# STM32_PCB_Design.net
KiCad netlist of a schematic drawn in Altium Designer
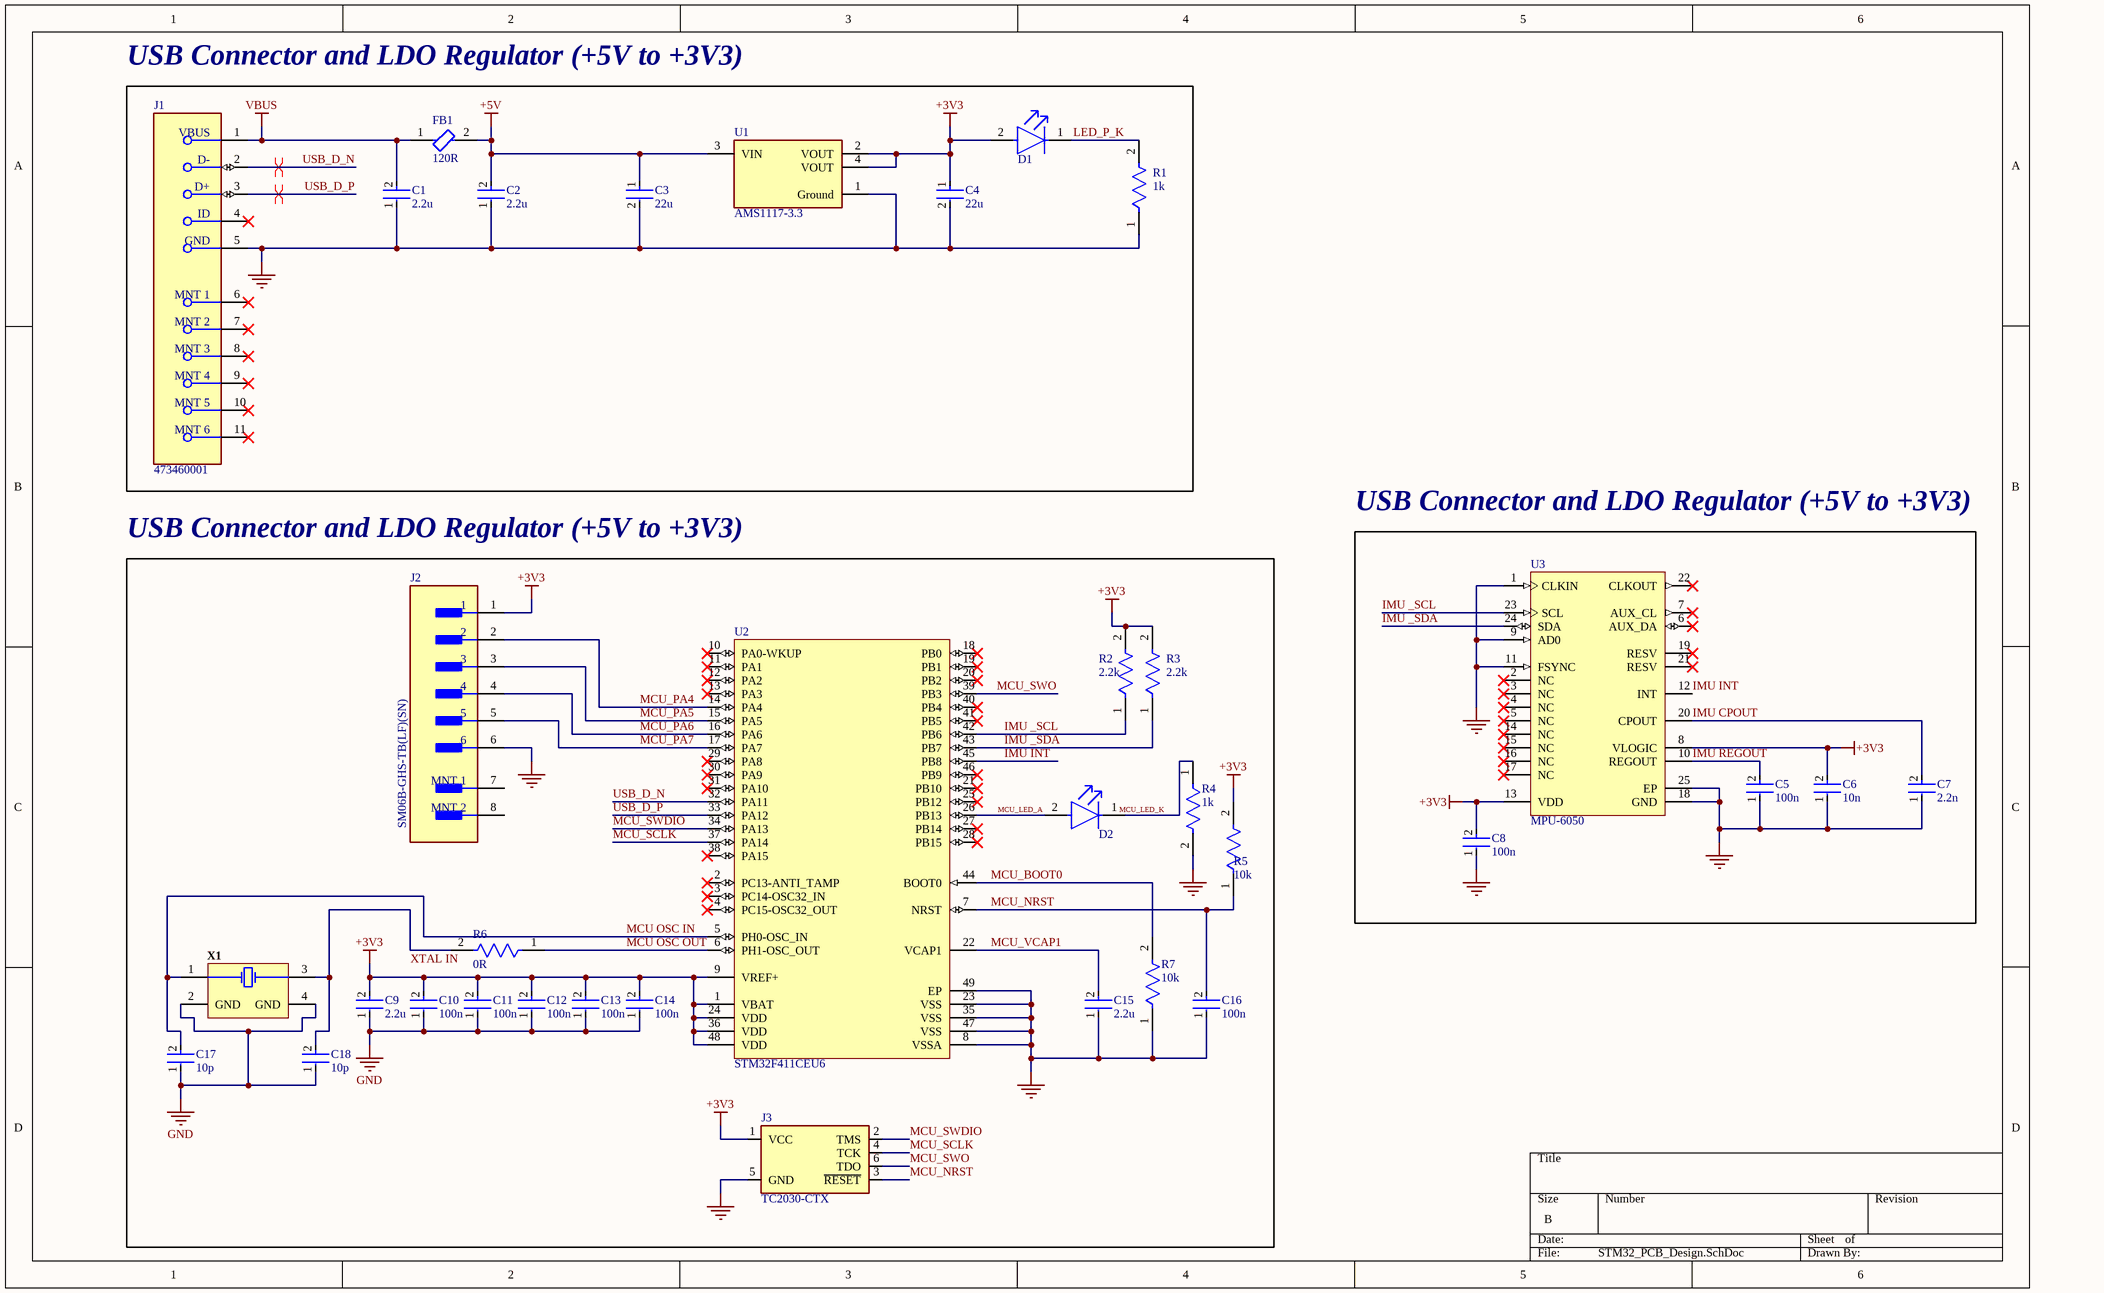
[diagram p0: STM32_PCB_Design.SchDoc]

(export (version "E")
  (design (tool "Eeschema 10.0.6"))
  (components
    (comp (ref "C1")
      (value "2.2u")
      (footprint "FP-GRM15-MFG")
      (description "CAP CER 0.1UF 16V X7R 0402")
      (fields (field (name "MANUFACTURER PART NUMBER") "GRM155R71C104KA88D") (field (name "TOLERANCE") "10%"))
      (libsource (lib "Altium Content Vault") (part "236180d848d6139a670b325ea6854c9"))
    )
    (comp (ref "C2")
      (value "2.2u")
      (footprint "FP-GRM15-MFG")
      (description "CAP CER 0.1UF 16V X7R 0402")
      (fields (field (name "MANUFACTURER PART NUMBER") "GRM155R71C104KA88D") (field (name "TOLERANCE") "10%"))
      (libsource (lib "Altium Content Vault") (part "236180d848d6139a670b325ea6854c9"))
    )
    (comp (ref "C3")
      (value "22u")
      (footprint "FP-0805-L_2_01_0_2-W_1_25-IPC_C")
      (description "General Purpose Ceramic Capacitor, 0805, 100nF, 10%, X7R, 0.15, 50V")
      (fields (field (name "TOLERANCE") "10%") (field (name "VOLTAGE") "50V"))
      (libsource (lib "Altium Content Vault") (part "02cd4be3c70576c341d710602a673aa"))
    )
    (comp (ref "C4")
      (value "22u")
      (footprint "FP-0805-L_2_01_0_2-W_1_25-IPC_C")
      (description "General Purpose Ceramic Capacitor, 0805, 100nF, 10%, X7R, 0.15, 50V")
      (fields (field (name "TOLERANCE") "10%") (field (name "VOLTAGE") "50V"))
      (libsource (lib "Altium Content Vault") (part "02cd4be3c70576c341d710602a673aa"))
    )
    (comp (ref "C5")
      (value "100n")
      (footprint "FP-GRM15-MFG")
      (description "CAP CER 0.1UF 16V X7R 0402")
      (fields (field (name "MANUFACTURER PART NUMBER") "GRM155R71C104KA88D") (field (name "TOLERANCE") "10%"))
      (libsource (lib "Altium Content Vault") (part "236180d848d6139a670b325ea6854c9"))
    )
    (comp (ref "C6")
      (value "10n")
      (footprint "FP-GRM15-MFG")
      (description "CAP CER 0.1UF 16V X7R 0402")
      (fields (field (name "MANUFACTURER PART NUMBER") "GRM155R71C104KA88D") (field (name "TOLERANCE") "10%"))
      (libsource (lib "Altium Content Vault") (part "236180d848d6139a670b325ea6854c9"))
    )
    (comp (ref "C7")
      (value "2.2n")
      (footprint "FP-GRM15-MFG")
      (description "CAP CER 0.1UF 16V X7R 0402")
      (fields (field (name "MANUFACTURER PART NUMBER") "GRM155R71C104KA88D") (field (name "TOLERANCE") "10%"))
      (libsource (lib "Altium Content Vault") (part "236180d848d6139a670b325ea6854c9"))
    )
    (comp (ref "C8")
      (value "100n")
      (footprint "FP-GRM15-MFG")
      (description "CAP CER 0.1UF 16V X7R 0402")
      (fields (field (name "MANUFACTURER PART NUMBER") "GRM155R71C104KA88D") (field (name "TOLERANCE") "10%"))
      (libsource (lib "Altium Content Vault") (part "236180d848d6139a670b325ea6854c9"))
    )
    (comp (ref "C9")
      (value "2.2u")
      (footprint "FP-GRM15-MFG")
      (description "CAP CER 0.1UF 16V X7R 0402")
      (fields (field (name "MANUFACTURER PART NUMBER") "GRM155R71C104KA88D") (field (name "TOLERANCE") "10%"))
      (libsource (lib "Altium Content Vault") (part "236180d848d6139a670b325ea6854c9"))
    )
    (comp (ref "C10")
      (value "100n")
      (footprint "FP-GRM15-MFG")
      (description "CAP CER 0.1UF 16V X7R 0402")
      (fields (field (name "MANUFACTURER PART NUMBER") "GRM155R71C104KA88D") (field (name "TOLERANCE") "10%"))
      (libsource (lib "Altium Content Vault") (part "236180d848d6139a670b325ea6854c9"))
    )
    (comp (ref "C11")
      (value "100n")
      (footprint "FP-GRM15-MFG")
      (description "CAP CER 0.1UF 16V X7R 0402")
      (fields (field (name "MANUFACTURER PART NUMBER") "GRM155R71C104KA88D") (field (name "TOLERANCE") "10%"))
      (libsource (lib "Altium Content Vault") (part "236180d848d6139a670b325ea6854c9"))
    )
    (comp (ref "C12")
      (value "100n")
      (footprint "FP-GRM15-MFG")
      (description "CAP CER 0.1UF 16V X7R 0402")
      (fields (field (name "MANUFACTURER PART NUMBER") "GRM155R71C104KA88D") (field (name "TOLERANCE") "10%"))
      (libsource (lib "Altium Content Vault") (part "236180d848d6139a670b325ea6854c9"))
    )
    (comp (ref "C13")
      (value "100n")
      (footprint "FP-GRM15-MFG")
      (description "CAP CER 0.1UF 16V X7R 0402")
      (fields (field (name "MANUFACTURER PART NUMBER") "GRM155R71C104KA88D") (field (name "TOLERANCE") "10%"))
      (libsource (lib "Altium Content Vault") (part "236180d848d6139a670b325ea6854c9"))
    )
    (comp (ref "C14")
      (value "100n")
      (footprint "FP-GRM15-MFG")
      (description "CAP CER 0.1UF 16V X7R 0402")
      (fields (field (name "MANUFACTURER PART NUMBER") "GRM155R71C104KA88D") (field (name "TOLERANCE") "10%"))
      (libsource (lib "Altium Content Vault") (part "236180d848d6139a670b325ea6854c9"))
    )
    (comp (ref "C15")
      (value "2.2u")
      (footprint "FP-GRM15-MFG")
      (description "CAP CER 0.1UF 16V X7R 0402")
      (fields (field (name "MANUFACTURER PART NUMBER") "GRM155R71C104KA88D") (field (name "TOLERANCE") "10%"))
      (libsource (lib "Altium Content Vault") (part "236180d848d6139a670b325ea6854c9"))
    )
    (comp (ref "C16")
      (value "100n")
      (footprint "FP-GRM15-MFG")
      (description "CAP CER 0.1UF 16V X7R 0402")
      (fields (field (name "MANUFACTURER PART NUMBER") "GRM155R71C104KA88D") (field (name "TOLERANCE") "10%"))
      (libsource (lib "Altium Content Vault") (part "236180d848d6139a670b325ea6854c9"))
    )
    (comp (ref "C17")
      (value "10p")
      (footprint "FP-GRM15-MFG")
      (description "CAP CER 0.1UF 16V X7R 0402")
      (fields (field (name "MANUFACTURER PART NUMBER") "GRM155R71C104KA88D") (field (name "TOLERANCE") "10%"))
      (libsource (lib "Altium Content Vault") (part "236180d848d6139a670b325ea6854c9"))
    )
    (comp (ref "C18")
      (value "10p")
      (footprint "FP-GRM15-MFG")
      (description "CAP CER 0.1UF 16V X7R 0402")
      (fields (field (name "MANUFACTURER PART NUMBER") "GRM155R71C104KA88D") (field (name "TOLERANCE") "10%"))
      (libsource (lib "Altium Content Vault") (part "236180d848d6139a670b325ea6854c9"))
    )
    (comp (ref "D1")
      (value "SML-P11MTT86")
      (footprint "FP-SML-P11MTT86-MFG")
      (description "LED YELLOW/GREEN CLEAR 1006 SMD")
      (libsource (lib "Altium Content Vault") (part "8706943c75ba83719d021d2fdc84c58"))
    )
    (comp (ref "D2")
      (value "SML-P11UTT86")
      (footprint "FP-SML-P11UTT86-MFG")
      (description "LED RED CLEAR 1006 SMD")
      (libsource (lib "Altium Content Vault") (part "8706943c75ba83719d021d2fdc84c58"))
    )
    (comp (ref "FB1")
      (value "120R")
      (footprint "FP-BLM18-0_15-t0_8-IPC_C")
      (description "Chip Ferrite Bead, 0603, 5Ω @ 100MHz, 0.05Ω, 25%, 800mA")
      (fields (field (name "TOLERANCE") "25%"))
      (libsource (lib "Altium Content Vault") (part "5f30dd21d616792df468990f7003faa"))
    )
    (comp (ref "J1")
      (value "473460001")
      (footprint "FP-473460001-MFG")
      (description "CONN RCPT USB2.0 MICRO B SMD R/A")
      (fields
        (field (name "OCTOPART") "https://octopart.com/47346-0001-molex-7164928")
        (field (name "MANUFACTURER") "Molex")
      )
      (libsource (lib "Altium Content Vault") (part "53ae1f1d9b557310b43ca686e5bb76a"))
    )
    (comp (ref "J2")
      (value "SM06B-GHS-TB(LF)(SN)")
      (footprint "FP-SM06B-GHS-TB_LF_SN-MFG")
      (description "CONN HEADER SMD R/A 6POS 1.25MM")
      (libsource (lib "Altium Content Vault") (part "ed24c53d9ba001d1a2a686240a95171"))
    )
    (comp (ref "J3")
      (value "TC2030-CTX")
      (footprint "TC2030-IDC-NL")
      (description "CortexÂ® Plug-Of-Nailsâ„¢ Adapter Cable")
      (fields (field (name "MF") "Tag-Connect LLC"))
      (libsource (lib "Akhila Prabodha") (part "TC2030-CTX"))
    )
    (comp (ref "R1")
      (value "1k")
      (footprint "FP-CRCW0402-e3-IPC_C")
      (description "RES Thick Film, 0Ω, 0.063W, 0402")
      (fields (field (name "TOLERANCE") "5%"))
      (libsource (lib "Altium Content Vault") (part "1029c3af85768c4190bb7ad29bc67b5"))
    )
    (comp (ref "R2")
      (value "2.2k")
      (footprint "FP-CRCW0402-e3-IPC_C")
      (description "RES Thick Film, 0Ω, 0.063W, 0402")
      (fields (field (name "TOLERANCE") "5%"))
      (libsource (lib "Altium Content Vault") (part "1029c3af85768c4190bb7ad29bc67b5"))
    )
    (comp (ref "R3")
      (value "2.2k")
      (footprint "FP-CRCW0402-e3-IPC_C")
      (description "RES Thick Film, 0Ω, 0.063W, 0402")
      (fields (field (name "TOLERANCE") "5%"))
      (libsource (lib "Altium Content Vault") (part "1029c3af85768c4190bb7ad29bc67b5"))
    )
    (comp (ref "R4")
      (value "1k")
      (footprint "FP-CRCW0402-e3-IPC_C")
      (description "RES Thick Film, 0Ω, 0.063W, 0402")
      (fields (field (name "TOLERANCE") "5%"))
      (libsource (lib "Altium Content Vault") (part "1029c3af85768c4190bb7ad29bc67b5"))
    )
    (comp (ref "R5")
      (value "10k")
      (footprint "FP-CRCW0402-e3-IPC_C")
      (description "RES Thick Film, 0Ω, 0.063W, 0402")
      (fields (field (name "TOLERANCE") "5%"))
      (libsource (lib "Altium Content Vault") (part "1029c3af85768c4190bb7ad29bc67b5"))
    )
    (comp (ref "R6")
      (value "0R")
      (footprint "FP-CRCW0402-e3-IPC_C")
      (description "RES Thick Film, 0Ω, 0.063W, 0402")
      (fields (field (name "TOLERANCE") "5%"))
      (libsource (lib "Altium Content Vault") (part "1029c3af85768c4190bb7ad29bc67b5"))
    )
    (comp (ref "R7")
      (value "10k")
      (footprint "FP-CRCW0402-e3-IPC_C")
      (description "RES Thick Film, 0Ω, 0.063W, 0402")
      (fields (field (name "TOLERANCE") "5%"))
      (libsource (lib "Altium Content Vault") (part "1029c3af85768c4190bb7ad29bc67b5"))
    )
    (comp (ref "U1")
      (value "AMS1117-3.3")
      (footprint "FP-AMS1117-IPC_C")
      (description "LDO Voltage Regulators 1A, 3.3V")
      (fields
        (field (name "OCTOPART") "https://octopart.com/ams1117-3.3-advanced+monolithic+systems-25899300")
        (field (name "MANUFACTURER") "Advanced Monolithic Systems")
      )
      (libsource (lib "Altium Content Vault") (part "8bdbb5f8e77002000e30dd2845d0354"))
    )
    (comp (ref "U2")
      (value "STM32F411CEU6")
      (footprint "STM-UFQFPN48_L")
      (libsource (lib "Altium Content Vault") (part "MC-ARM-STM32F411-UFQFPN48"))
    )
    (comp (ref "U3")
      (value "MPU-6050")
      (footprint "IS-QFN-24_V")
      (fields (field (name "MANUFACTURER") "InvenSense"))
      (libsource (lib "Altium Content Vault") (part "IS-MPU-6050-QFN-24"))
    )
    (comp (ref "X1")
      (value "TSX-3225 24.0000MF15X-AC3")
      (footprint "EPSON-TSX-3225_V")
      (description "MHz Range Crystal, 24 MHz, -40 to 85 degC, 4-Pin SMD, RoHS, Tape and Reel")
      (fields (field (name "TOLERANCE") "10PPM") (field (name "MANUFACTURER") "Epson"))
      (libsource (lib "Altium Content Vault") (part "XTAL-1-3-4"))
    )
  )
  (nets
    (net (code "1") (name "+3V3") (class "Default")
      (node (ref "C10") (pin "2") (pinfunction "2_2") (pintype "passive"))
      (node (ref "C11") (pin "2") (pinfunction "2_2") (pintype "passive"))
      (node (ref "C12") (pin "2") (pinfunction "2_2") (pintype "passive"))
      (node (ref "C13") (pin "2") (pinfunction "2_2") (pintype "passive"))
      (node (ref "C14") (pin "2") (pinfunction "2_2") (pintype "passive"))
      (node (ref "C4") (pin "1") (pinfunction "1_1") (pintype "passive"))
      (node (ref "C6") (pin "2") (pinfunction "2_2") (pintype "passive"))
      (node (ref "C8") (pin "2") (pinfunction "2_2") (pintype "passive"))
      (node (ref "C9") (pin "2") (pinfunction "2_2") (pintype "passive"))
      (node (ref "D1") (pin "2") (pinfunction "A_2") (pintype "passive"))
      (node (ref "J2") (pin "1") (pinfunction "1_1") (pintype "passive"))
      (node (ref "J3") (pin "1") (pinfunction "VCC_1") (pintype "bidirectional"))
      (node (ref "R2") (pin "2") (pinfunction "2_2") (pintype "passive"))
      (node (ref "R3") (pin "2") (pinfunction "2_2") (pintype "passive"))
      (node (ref "R5") (pin "2") (pinfunction "2_2") (pintype "passive"))
      (node (ref "U1") (pin "2") (pinfunction "VOUT_2") (pintype "passive"))
      (node (ref "U1") (pin "4") (pinfunction "VOUT_4") (pintype "passive"))
      (node (ref "U2") (pin "1") (pinfunction "VBAT_1") (pintype "power_in"))
      (node (ref "U2") (pin "24") (pinfunction "VDD_24") (pintype "power_in"))
      (node (ref "U2") (pin "36") (pinfunction "VDD_36") (pintype "power_in"))
      (node (ref "U2") (pin "48") (pinfunction "VDD_48") (pintype "power_in"))
      (node (ref "U2") (pin "9") (pinfunction "VREF+_9") (pintype "power_in"))
      (node (ref "U3") (pin "13") (pinfunction "VDD_13") (pintype "power_in"))
      (node (ref "U3") (pin "8") (pinfunction "VLOGIC_8") (pintype "power_in"))
    )
    (net (code "2") (name "+5V") (class "Default")
      (node (ref "C2") (pin "2") (pinfunction "2_2") (pintype "passive"))
      (node (ref "C3") (pin "1") (pinfunction "1_1") (pintype "passive"))
      (node (ref "FB1") (pin "2") (pinfunction "2_2") (pintype "passive"))
      (node (ref "U1") (pin "3") (pinfunction "VIN_3") (pintype "power_in"))
    )
    (net (code "3") (name "/IMU CPOUT") (class "Default")
      (node (ref "C7") (pin "2") (pinfunction "2_2") (pintype "passive"))
      (node (ref "U3") (pin "20") (pinfunction "CPOUT_20") (pintype "passive"))
    )
    (net (code "4") (name "/IMU INT") (class "Default")
      (node (ref "U2") (pin "45") (pinfunction "PB8_45") (pintype "bidirectional"))
      (node (ref "U3") (pin "12") (pinfunction "INT_12") (pintype "open_collector"))
    )
    (net (code "5") (name "/IMU REGOUT") (class "Default")
      (node (ref "C5") (pin "2") (pinfunction "2_2") (pintype "passive"))
      (node (ref "U3") (pin "10") (pinfunction "REGOUT_10") (pintype "passive"))
    )
    (net (code "6") (name "/IMU _SCL") (class "Default")
      (node (ref "R2") (pin "1") (pinfunction "1_1") (pintype "passive"))
      (node (ref "U2") (pin "42") (pinfunction "PB6_42") (pintype "bidirectional"))
      (node (ref "U3") (pin "23") (pinfunction "SCL_23") (pintype "input"))
    )
    (net (code "7") (name "/IMU _SDA") (class "Default")
      (node (ref "R3") (pin "1") (pinfunction "1_1") (pintype "passive"))
      (node (ref "U2") (pin "43") (pinfunction "PB7_43") (pintype "bidirectional"))
      (node (ref "U3") (pin "24") (pinfunction "SDA_24") (pintype "bidirectional"))
    )
    (net (code "8") (name "/LED_P_K") (class "Default")
      (node (ref "D1") (pin "1") (pinfunction "C_1") (pintype "passive"))
      (node (ref "R1") (pin "2") (pinfunction "2_2") (pintype "passive"))
    )
    (net (code "9") (name "/MCU OSC IN") (class "Default")
      (node (ref "C17") (pin "2") (pinfunction "2_2") (pintype "passive"))
      (node (ref "U2") (pin "5") (pinfunction "PH0-OSC_IN_5") (pintype "bidirectional"))
      (node (ref "X1") (pin "1") (pinfunction "X1_1") (pintype "passive"))
    )
    (net (code "10") (name "/MCU OSC OUT") (class "Default")
      (node (ref "R6") (pin "1") (pinfunction "1_1") (pintype "passive"))
      (node (ref "U2") (pin "6") (pinfunction "PH1-OSC_OUT_6") (pintype "bidirectional"))
    )
    (net (code "11") (name "/MCU_BOOT0") (class "Default")
      (node (ref "R7") (pin "2") (pinfunction "2_2") (pintype "passive"))
      (node (ref "U2") (pin "44") (pinfunction "BOOT0_44") (pintype "input"))
    )
    (net (code "12") (name "/MCU_LED_A") (class "Default")
      (node (ref "D2") (pin "2") (pinfunction "A_2") (pintype "passive"))
      (node (ref "U2") (pin "26") (pinfunction "PB13_26") (pintype "bidirectional"))
    )
    (net (code "13") (name "/MCU_LED_K") (class "Default")
      (node (ref "D2") (pin "1") (pinfunction "C_1") (pintype "passive"))
      (node (ref "R4") (pin "1") (pinfunction "1_1") (pintype "passive"))
    )
    (net (code "14") (name "/MCU_NRST") (class "Default")
      (node (ref "C16") (pin "2") (pinfunction "2_2") (pintype "passive"))
      (node (ref "J3") (pin "3") (pinfunction "~{RESET}_3") (pintype "bidirectional"))
      (node (ref "R5") (pin "1") (pinfunction "1_1") (pintype "passive"))
      (node (ref "U2") (pin "7") (pinfunction "NRST_7") (pintype "bidirectional"))
    )
    (net (code "15") (name "/MCU_PA4") (class "Default")
      (node (ref "J2") (pin "2") (pinfunction "2_2") (pintype "passive"))
      (node (ref "U2") (pin "14") (pinfunction "PA4_14") (pintype "bidirectional"))
    )
    (net (code "16") (name "/MCU_PA5") (class "Default")
      (node (ref "J2") (pin "3") (pinfunction "3_3") (pintype "passive"))
      (node (ref "U2") (pin "15") (pinfunction "PA5_15") (pintype "bidirectional"))
    )
    (net (code "17") (name "/MCU_PA6") (class "Default")
      (node (ref "J2") (pin "4") (pinfunction "4_4") (pintype "passive"))
      (node (ref "U2") (pin "16") (pinfunction "PA6_16") (pintype "bidirectional"))
    )
    (net (code "18") (name "/MCU_PA7") (class "Default")
      (node (ref "J2") (pin "5") (pinfunction "5_5") (pintype "passive"))
      (node (ref "U2") (pin "17") (pinfunction "PA7_17") (pintype "bidirectional"))
    )
    (net (code "19") (name "/MCU_SCLK") (class "Default")
      (node (ref "J3") (pin "4") (pinfunction "TCK_4") (pintype "bidirectional"))
      (node (ref "U2") (pin "37") (pinfunction "PA14_37") (pintype "bidirectional"))
    )
    (net (code "20") (name "/MCU_SWDIO") (class "Default")
      (node (ref "J3") (pin "2") (pinfunction "TMS_2") (pintype "bidirectional"))
      (node (ref "U2") (pin "34") (pinfunction "PA13_34") (pintype "bidirectional"))
    )
    (net (code "21") (name "/MCU_SWO") (class "Default")
      (node (ref "J3") (pin "6") (pinfunction "TDO_6") (pintype "bidirectional"))
      (node (ref "U2") (pin "39") (pinfunction "PB3_39") (pintype "bidirectional"))
    )
    (net (code "22") (name "/MCU_VCAP1") (class "Default")
      (node (ref "C15") (pin "2") (pinfunction "2_2") (pintype "passive"))
      (node (ref "U2") (pin "22") (pinfunction "VCAP1_22") (pintype "passive"))
    )
    (net (code "23") (name "/USB_D_N") (class "Default")
      (node (ref "J1") (pin "2") (pinfunction "D-_2") (pintype "bidirectional"))
      (node (ref "U2") (pin "32") (pinfunction "PA11_32") (pintype "bidirectional"))
    )
    (net (code "24") (name "/USB_D_P") (class "Default")
      (node (ref "J1") (pin "3") (pinfunction "D+_3") (pintype "bidirectional"))
      (node (ref "U2") (pin "33") (pinfunction "PA12_33") (pintype "bidirectional"))
    )
    (net (code "25") (name "/XTAL IN") (class "Default")
      (node (ref "C18") (pin "2") (pinfunction "2_2") (pintype "passive"))
      (node (ref "R6") (pin "2") (pinfunction "2_2") (pintype "passive"))
      (node (ref "X1") (pin "3") (pinfunction "X2_3") (pintype "passive"))
    )
    (net (code "26") (name "GND") (class "Default")
      (node (ref "C1") (pin "1") (pinfunction "1_1") (pintype "passive"))
      (node (ref "C10") (pin "1") (pinfunction "1_1") (pintype "passive"))
      (node (ref "C11") (pin "1") (pinfunction "1_1") (pintype "passive"))
      (node (ref "C12") (pin "1") (pinfunction "1_1") (pintype "passive"))
      (node (ref "C13") (pin "1") (pinfunction "1_1") (pintype "passive"))
      (node (ref "C14") (pin "1") (pinfunction "1_1") (pintype "passive"))
      (node (ref "C15") (pin "1") (pinfunction "1_1") (pintype "passive"))
      (node (ref "C16") (pin "1") (pinfunction "1_1") (pintype "passive"))
      (node (ref "C17") (pin "1") (pinfunction "1_1") (pintype "passive"))
      (node (ref "C18") (pin "1") (pinfunction "1_1") (pintype "passive"))
      (node (ref "C2") (pin "1") (pinfunction "1_1") (pintype "passive"))
      (node (ref "C3") (pin "2") (pinfunction "2_2") (pintype "passive"))
      (node (ref "C4") (pin "2") (pinfunction "2_2") (pintype "passive"))
      (node (ref "C5") (pin "1") (pinfunction "1_1") (pintype "passive"))
      (node (ref "C6") (pin "1") (pinfunction "1_1") (pintype "passive"))
      (node (ref "C7") (pin "1") (pinfunction "1_1") (pintype "passive"))
      (node (ref "C8") (pin "1") (pinfunction "1_1") (pintype "passive"))
      (node (ref "C9") (pin "1") (pinfunction "1_1") (pintype "passive"))
      (node (ref "J1") (pin "5") (pinfunction "GND_5") (pintype "power_in"))
      (node (ref "J2") (pin "6") (pinfunction "6_6") (pintype "passive"))
      (node (ref "J3") (pin "5") (pinfunction "GND_5") (pintype "bidirectional"))
      (node (ref "R1") (pin "1") (pinfunction "1_1") (pintype "passive"))
      (node (ref "R4") (pin "2") (pinfunction "2_2") (pintype "passive"))
      (node (ref "R7") (pin "1") (pinfunction "1_1") (pintype "passive"))
      (node (ref "U1") (pin "1") (pinfunction "Ground_1") (pintype "power_in"))
      (node (ref "U2") (pin "23") (pinfunction "VSS_23") (pintype "power_in"))
      (node (ref "U2") (pin "35") (pinfunction "VSS_35") (pintype "power_in"))
      (node (ref "U2") (pin "47") (pinfunction "VSS_47") (pintype "power_in"))
      (node (ref "U2") (pin "49") (pinfunction "EP_49") (pintype "power_in"))
      (node (ref "U2") (pin "8") (pinfunction "VSSA_8") (pintype "power_in"))
      (node (ref "U3") (pin "1") (pinfunction "CLKIN_1") (pintype "input"))
      (node (ref "U3") (pin "11") (pinfunction "FSYNC_11") (pintype "input"))
      (node (ref "U3") (pin "18") (pinfunction "GND_18") (pintype "power_in"))
      (node (ref "U3") (pin "25") (pinfunction "EP_25") (pintype "power_in"))
      (node (ref "U3") (pin "9") (pinfunction "AD0_9") (pintype "input"))
      (node (ref "X1") (pin "2") (pinfunction "GND_2") (pintype "power_in"))
      (node (ref "X1") (pin "4") (pinfunction "GND_4") (pintype "power_in"))
    )
    (net (code "27") (name "VBUS") (class "Default")
      (node (ref "C1") (pin "2") (pinfunction "2_2") (pintype "passive"))
      (node (ref "FB1") (pin "1") (pinfunction "1_1") (pintype "passive"))
      (node (ref "J1") (pin "1") (pinfunction "VBUS_1") (pintype "power_in"))
    )
    (net (code "28") (name "unconnected-(J1-ID-Pad4)") (class "Default")
      (node (ref "J1") (pin "4") (pinfunction "ID_4") (pintype "passive+no_connect"))
    )
    (net (code "29") (name "unconnected-(J1-MNT_1-Pad6)") (class "Default")
      (node (ref "J1") (pin "6") (pinfunction "MNT_1_6") (pintype "passive+no_connect"))
    )
    (net (code "30") (name "unconnected-(J1-MNT_2-Pad7)") (class "Default")
      (node (ref "J1") (pin "7") (pinfunction "MNT_2_7") (pintype "passive+no_connect"))
    )
    (net (code "31") (name "unconnected-(J1-MNT_3-Pad8)") (class "Default")
      (node (ref "J1") (pin "8") (pinfunction "MNT_3_8") (pintype "passive+no_connect"))
    )
    (net (code "32") (name "unconnected-(J1-MNT_4-Pad9)") (class "Default")
      (node (ref "J1") (pin "9") (pinfunction "MNT_4_9") (pintype "passive+no_connect"))
    )
    (net (code "33") (name "unconnected-(J1-MNT_5-Pad10)") (class "Default")
      (node (ref "J1") (pin "10") (pinfunction "MNT_5_10") (pintype "passive+no_connect"))
    )
    (net (code "34") (name "unconnected-(J1-MNT_6-Pad11)") (class "Default")
      (node (ref "J1") (pin "11") (pinfunction "MNT_6_11") (pintype "passive+no_connect"))
    )
    (net (code "35") (name "unconnected-(J2-MNT_1-Pad7)") (class "Default")
      (node (ref "J2") (pin "7") (pinfunction "MNT_1_7") (pintype "passive"))
    )
    (net (code "36") (name "unconnected-(J2-MNT_2-Pad8)") (class "Default")
      (node (ref "J2") (pin "8") (pinfunction "MNT_2_8") (pintype "passive"))
    )
    (net (code "37") (name "unconnected-(U2-PA0-WKUP-Pad10)") (class "Default")
      (node (ref "U2") (pin "10") (pinfunction "PA0-WKUP_10") (pintype "bidirectional+no_connect"))
    )
    (net (code "38") (name "unconnected-(U2-PA1-Pad11)") (class "Default")
      (node (ref "U2") (pin "11") (pinfunction "PA1_11") (pintype "bidirectional+no_connect"))
    )
    (net (code "39") (name "unconnected-(U2-PA2-Pad12)") (class "Default")
      (node (ref "U2") (pin "12") (pinfunction "PA2_12") (pintype "bidirectional+no_connect"))
    )
    (net (code "40") (name "unconnected-(U2-PA3-Pad13)") (class "Default")
      (node (ref "U2") (pin "13") (pinfunction "PA3_13") (pintype "bidirectional+no_connect"))
    )
    (net (code "41") (name "unconnected-(U2-PA8-Pad29)") (class "Default")
      (node (ref "U2") (pin "29") (pinfunction "PA8_29") (pintype "bidirectional+no_connect"))
    )
    (net (code "42") (name "unconnected-(U2-PA9-Pad30)") (class "Default")
      (node (ref "U2") (pin "30") (pinfunction "PA9_30") (pintype "bidirectional+no_connect"))
    )
    (net (code "43") (name "unconnected-(U2-PA10-Pad31)") (class "Default")
      (node (ref "U2") (pin "31") (pinfunction "PA10_31") (pintype "bidirectional+no_connect"))
    )
    (net (code "44") (name "unconnected-(U2-PA15-Pad38)") (class "Default")
      (node (ref "U2") (pin "38") (pinfunction "PA15_38") (pintype "bidirectional+no_connect"))
    )
    (net (code "45") (name "unconnected-(U2-PB0-Pad18)") (class "Default")
      (node (ref "U2") (pin "18") (pinfunction "PB0_18") (pintype "bidirectional+no_connect"))
    )
    (net (code "46") (name "unconnected-(U2-PB1-Pad19)") (class "Default")
      (node (ref "U2") (pin "19") (pinfunction "PB1_19") (pintype "bidirectional+no_connect"))
    )
    (net (code "47") (name "unconnected-(U2-PB2-Pad20)") (class "Default")
      (node (ref "U2") (pin "20") (pinfunction "PB2_20") (pintype "bidirectional+no_connect"))
    )
    (net (code "48") (name "unconnected-(U2-PB4-Pad40)") (class "Default")
      (node (ref "U2") (pin "40") (pinfunction "PB4_40") (pintype "bidirectional+no_connect"))
    )
    (net (code "49") (name "unconnected-(U2-PB5-Pad41)") (class "Default")
      (node (ref "U2") (pin "41") (pinfunction "PB5_41") (pintype "bidirectional+no_connect"))
    )
    (net (code "50") (name "unconnected-(U2-PB9-Pad46)") (class "Default")
      (node (ref "U2") (pin "46") (pinfunction "PB9_46") (pintype "bidirectional+no_connect"))
    )
    (net (code "51") (name "unconnected-(U2-PB10-Pad21)") (class "Default")
      (node (ref "U2") (pin "21") (pinfunction "PB10_21") (pintype "bidirectional+no_connect"))
    )
    (net (code "52") (name "unconnected-(U2-PB12-Pad25)") (class "Default")
      (node (ref "U2") (pin "25") (pinfunction "PB12_25") (pintype "bidirectional+no_connect"))
    )
    (net (code "53") (name "unconnected-(U2-PB14-Pad27)") (class "Default")
      (node (ref "U2") (pin "27") (pinfunction "PB14_27") (pintype "bidirectional+no_connect"))
    )
    (net (code "54") (name "unconnected-(U2-PB15-Pad28)") (class "Default")
      (node (ref "U2") (pin "28") (pinfunction "PB15_28") (pintype "bidirectional+no_connect"))
    )
    (net (code "55") (name "unconnected-(U2-PC13-ANTI_TAMP-Pad2)") (class "Default")
      (node (ref "U2") (pin "2") (pinfunction "PC13-ANTI_TAMP_2") (pintype "bidirectional+no_connect"))
    )
    (net (code "56") (name "unconnected-(U2-PC14-OSC32_IN-Pad3)") (class "Default")
      (node (ref "U2") (pin "3") (pinfunction "PC14-OSC32_IN_3") (pintype "bidirectional+no_connect"))
    )
    (net (code "57") (name "unconnected-(U2-PC15-OSC32_OUT-Pad4)") (class "Default")
      (node (ref "U2") (pin "4") (pinfunction "PC15-OSC32_OUT_4") (pintype "bidirectional+no_connect"))
    )
    (net (code "58") (name "unconnected-(U3-AUX_CL-Pad7)") (class "Default")
      (node (ref "U3") (pin "7") (pinfunction "AUX_CL_7") (pintype "output+no_connect"))
    )
    (net (code "59") (name "unconnected-(U3-AUX_DA-Pad6)") (class "Default")
      (node (ref "U3") (pin "6") (pinfunction "AUX_DA_6") (pintype "bidirectional+no_connect"))
    )
    (net (code "60") (name "unconnected-(U3-CLKOUT-Pad22)") (class "Default")
      (node (ref "U3") (pin "22") (pinfunction "CLKOUT_22") (pintype "output+no_connect"))
    )
    (net (code "61") (name "unconnected-(U3-NC-Pad2)") (class "Default")
      (node (ref "U3") (pin "2") (pinfunction "NC_2") (pintype "passive+no_connect"))
    )
    (net (code "62") (name "unconnected-(U3-NC-Pad3)") (class "Default")
      (node (ref "U3") (pin "3") (pinfunction "NC_3") (pintype "passive+no_connect"))
    )
    (net (code "63") (name "unconnected-(U3-NC-Pad4)") (class "Default")
      (node (ref "U3") (pin "4") (pinfunction "NC_4") (pintype "passive+no_connect"))
    )
    (net (code "64") (name "unconnected-(U3-NC-Pad5)") (class "Default")
      (node (ref "U3") (pin "5") (pinfunction "NC_5") (pintype "passive+no_connect"))
    )
    (net (code "65") (name "unconnected-(U3-NC-Pad14)") (class "Default")
      (node (ref "U3") (pin "14") (pinfunction "NC_14") (pintype "passive+no_connect"))
    )
    (net (code "66") (name "unconnected-(U3-NC-Pad15)") (class "Default")
      (node (ref "U3") (pin "15") (pinfunction "NC_15") (pintype "passive+no_connect"))
    )
    (net (code "67") (name "unconnected-(U3-NC-Pad16)") (class "Default")
      (node (ref "U3") (pin "16") (pinfunction "NC_16") (pintype "passive+no_connect"))
    )
    (net (code "68") (name "unconnected-(U3-NC-Pad17)") (class "Default")
      (node (ref "U3") (pin "17") (pinfunction "NC_17") (pintype "passive+no_connect"))
    )
    (net (code "69") (name "unconnected-(U3-RESV-Pad19)") (class "Default")
      (node (ref "U3") (pin "19") (pinfunction "RESV_19") (pintype "passive+no_connect"))
    )
    (net (code "70") (name "unconnected-(U3-RESV-Pad21)") (class "Default")
      (node (ref "U3") (pin "21") (pinfunction "RESV_21") (pintype "passive+no_connect"))
    )
  )
)
